# mrShark_11.net
KiCad netlist of a schematic drawn in EAGLE
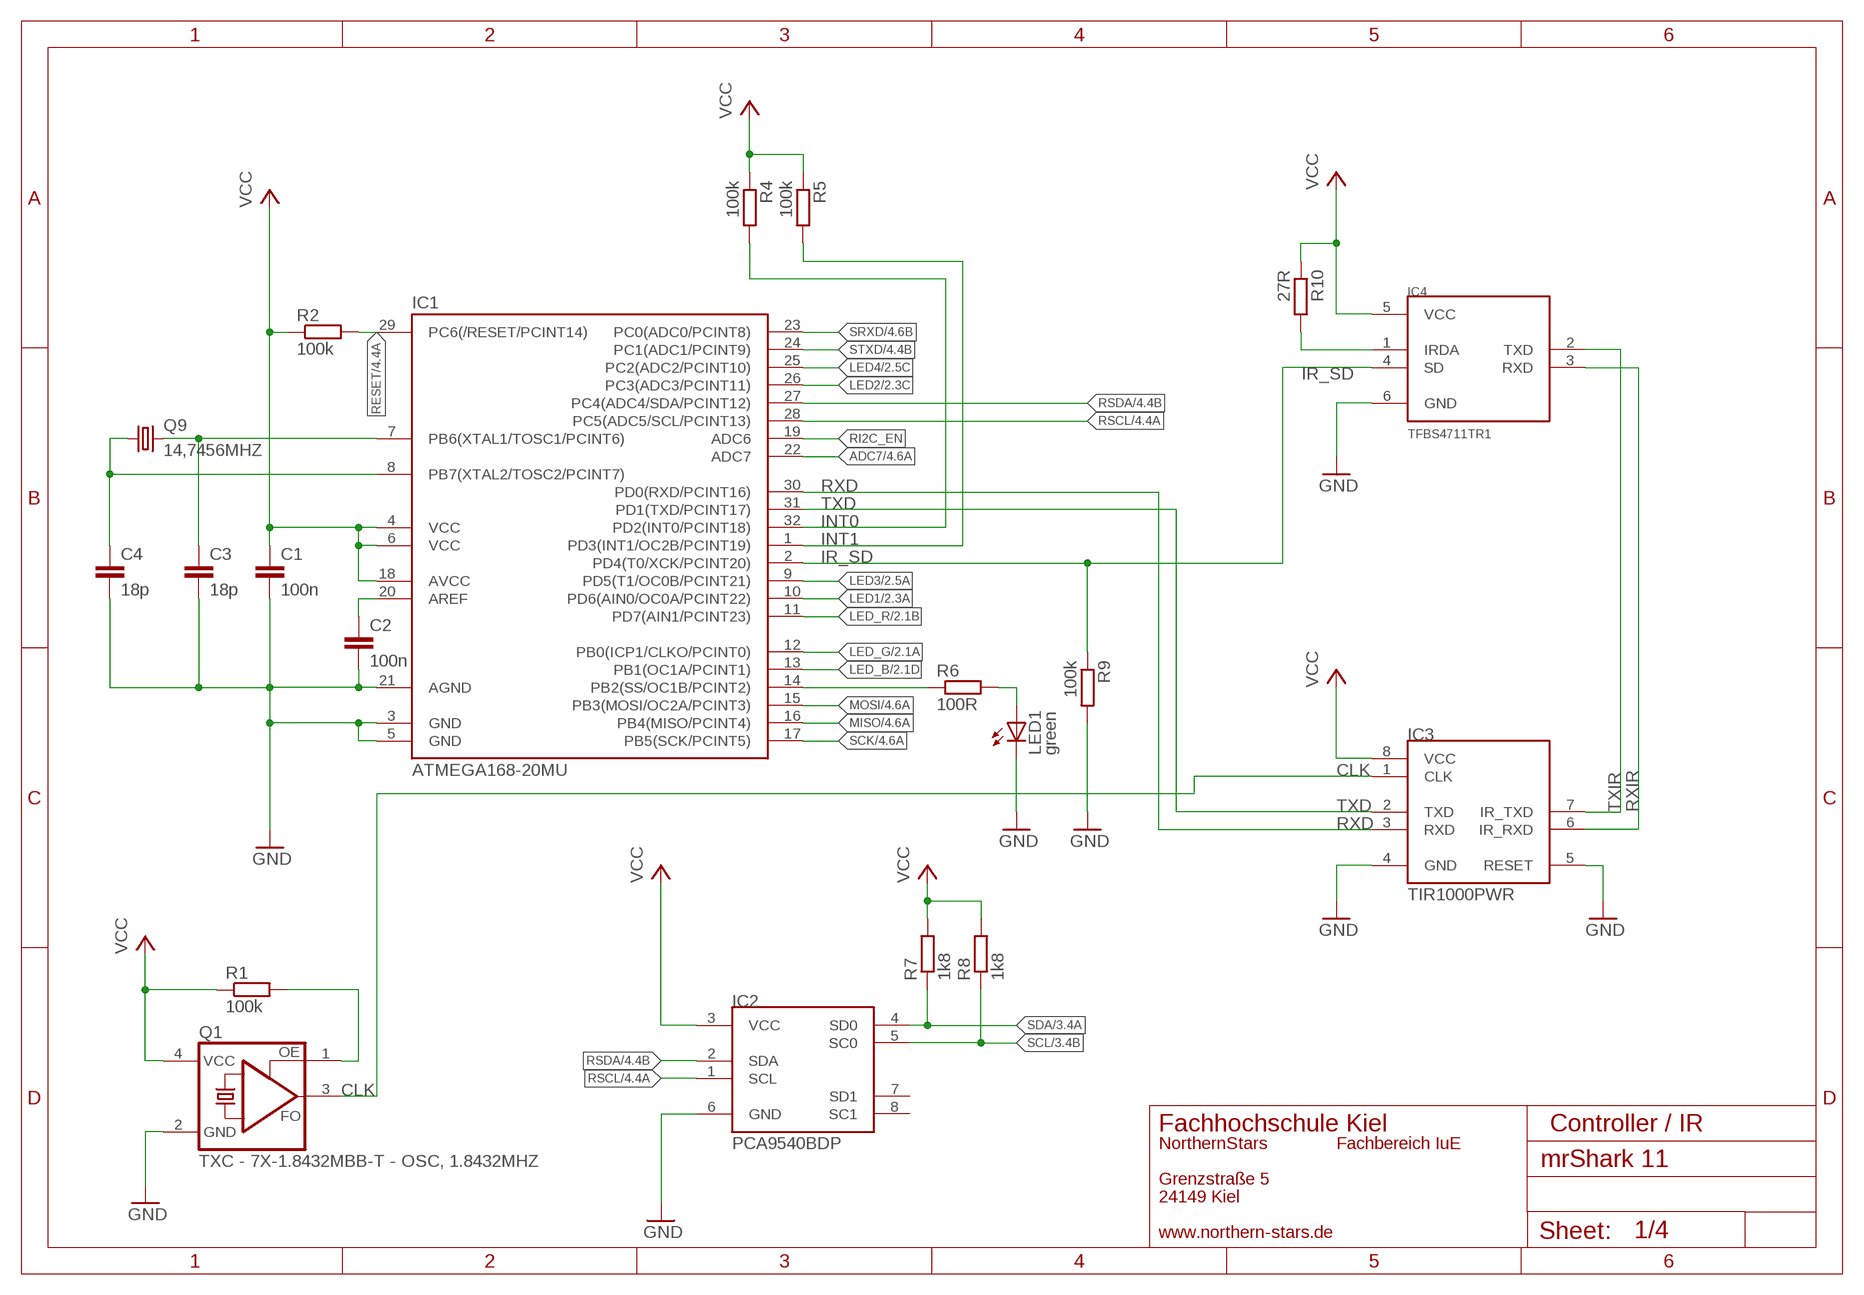
[diagram p0: schematic, sheet 1]
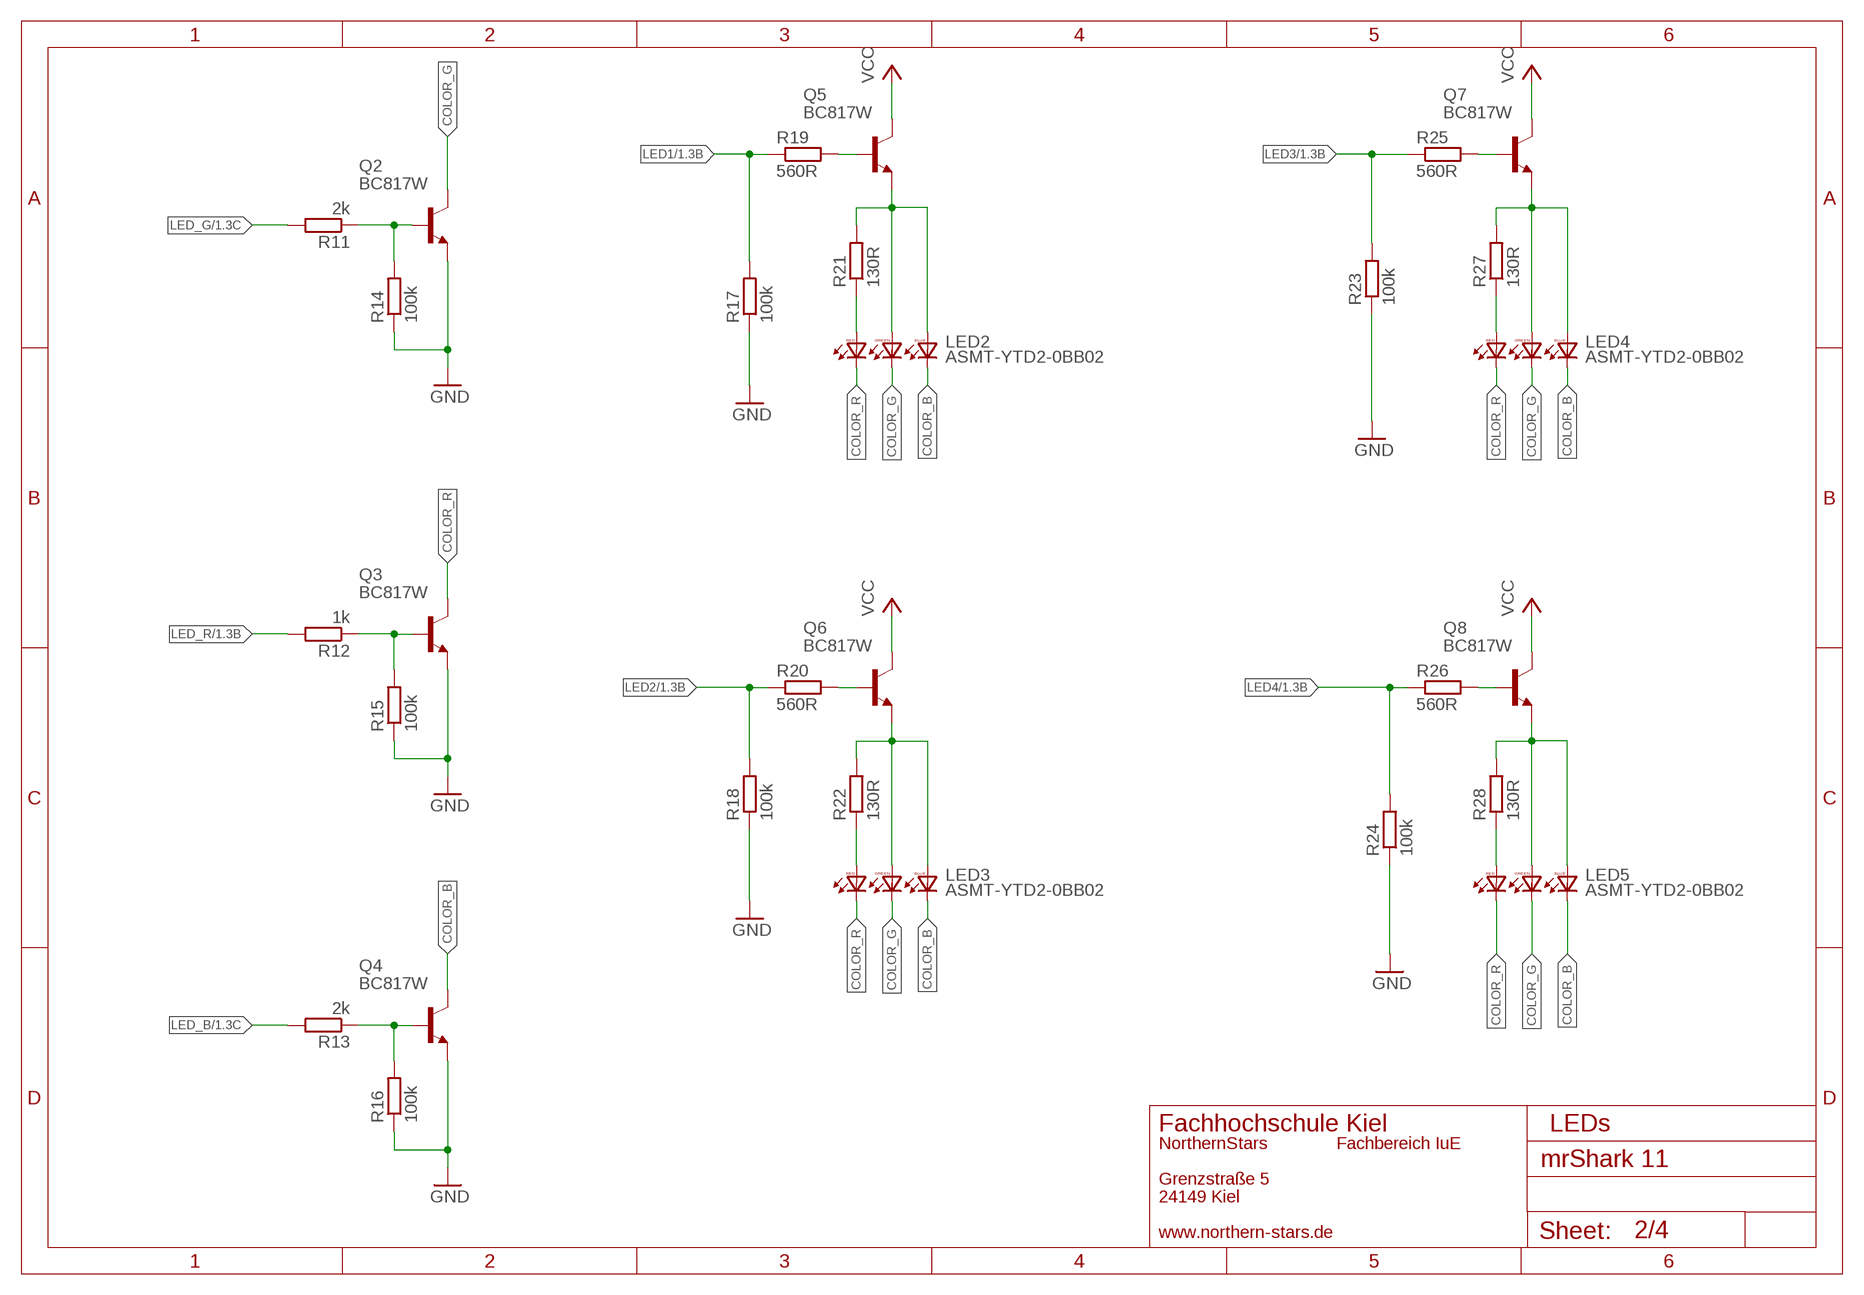
[diagram p1: schematic, sheet 2]
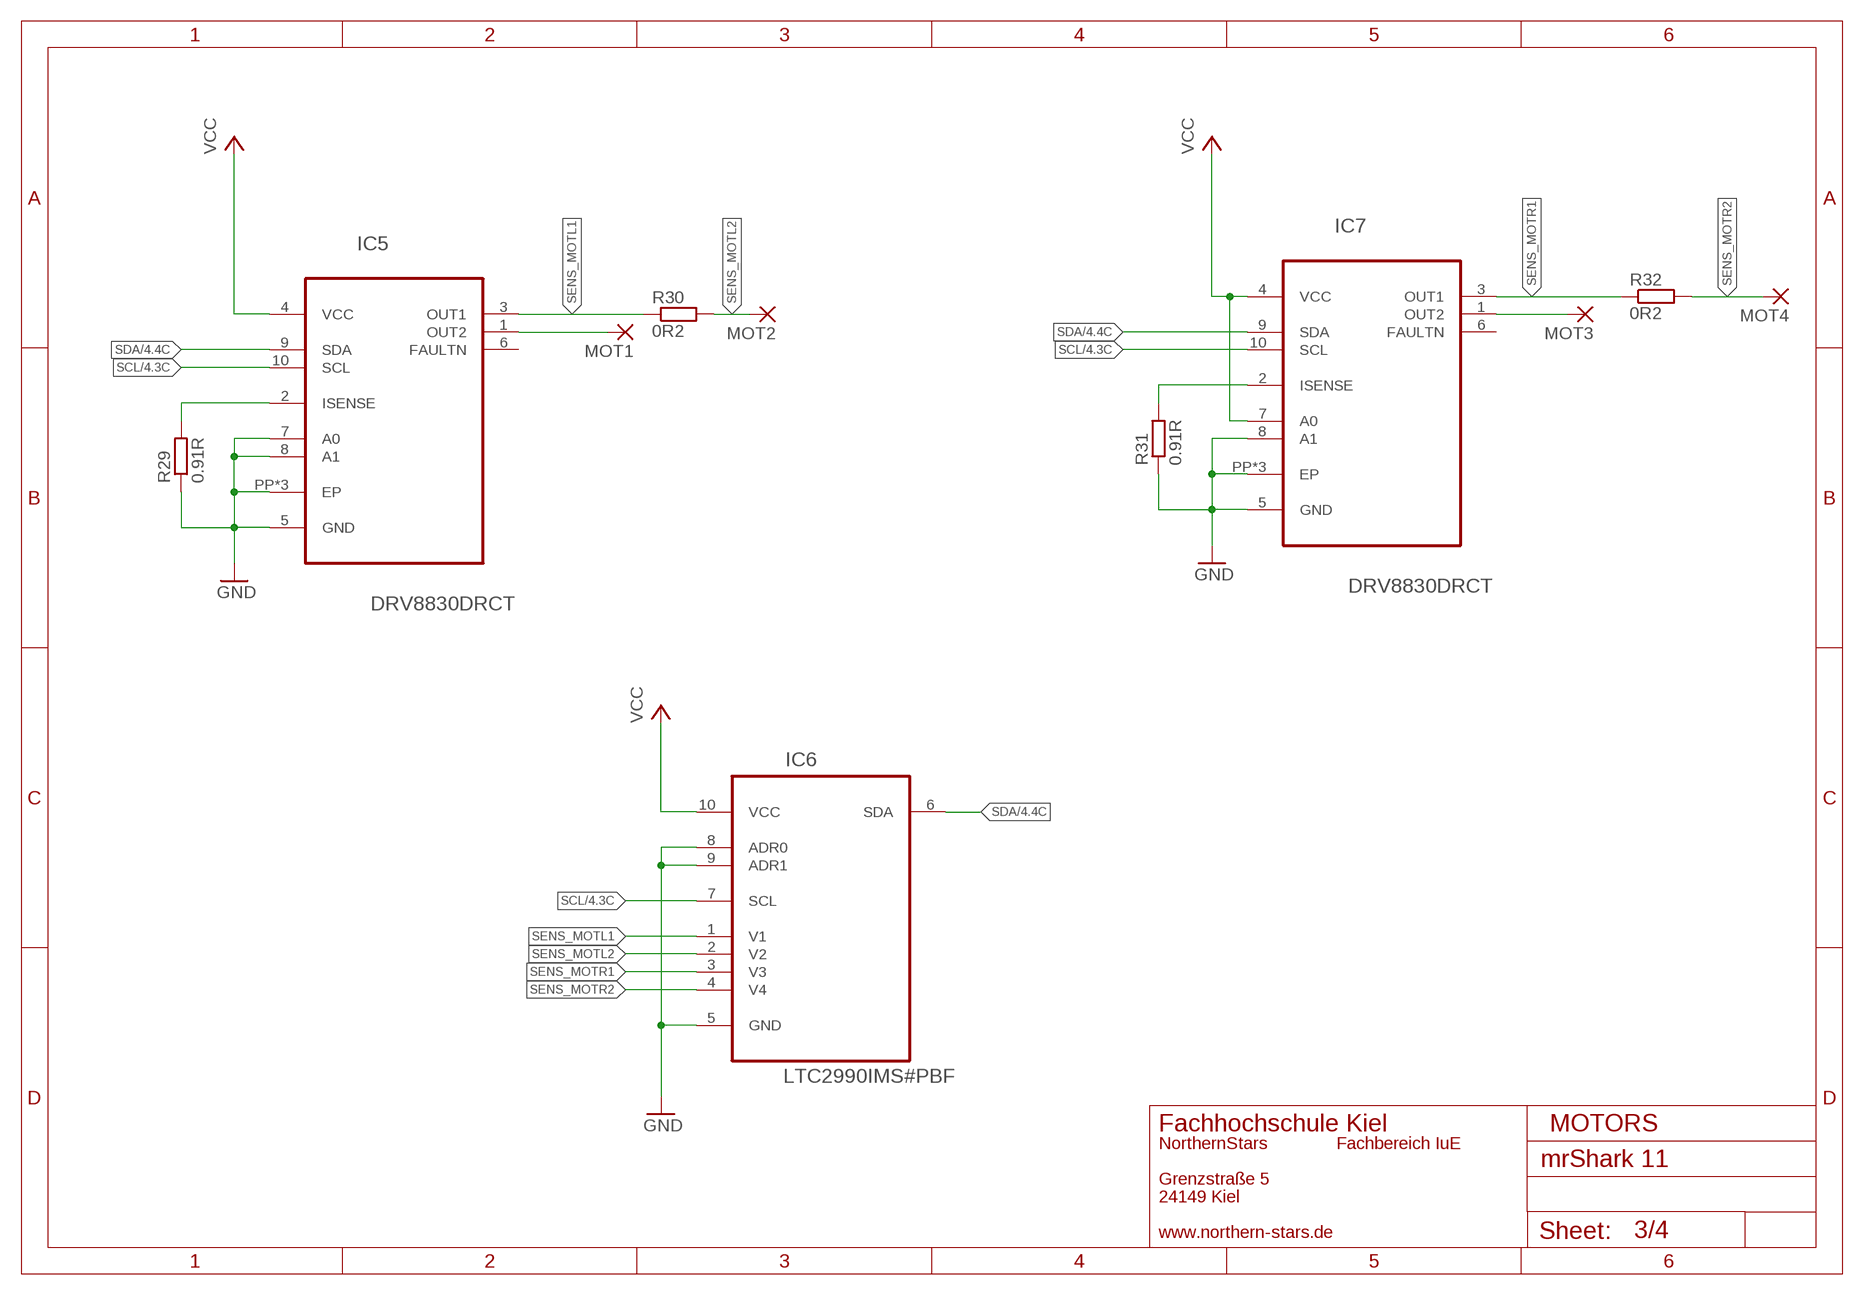
[diagram p2: schematic, sheet 3]
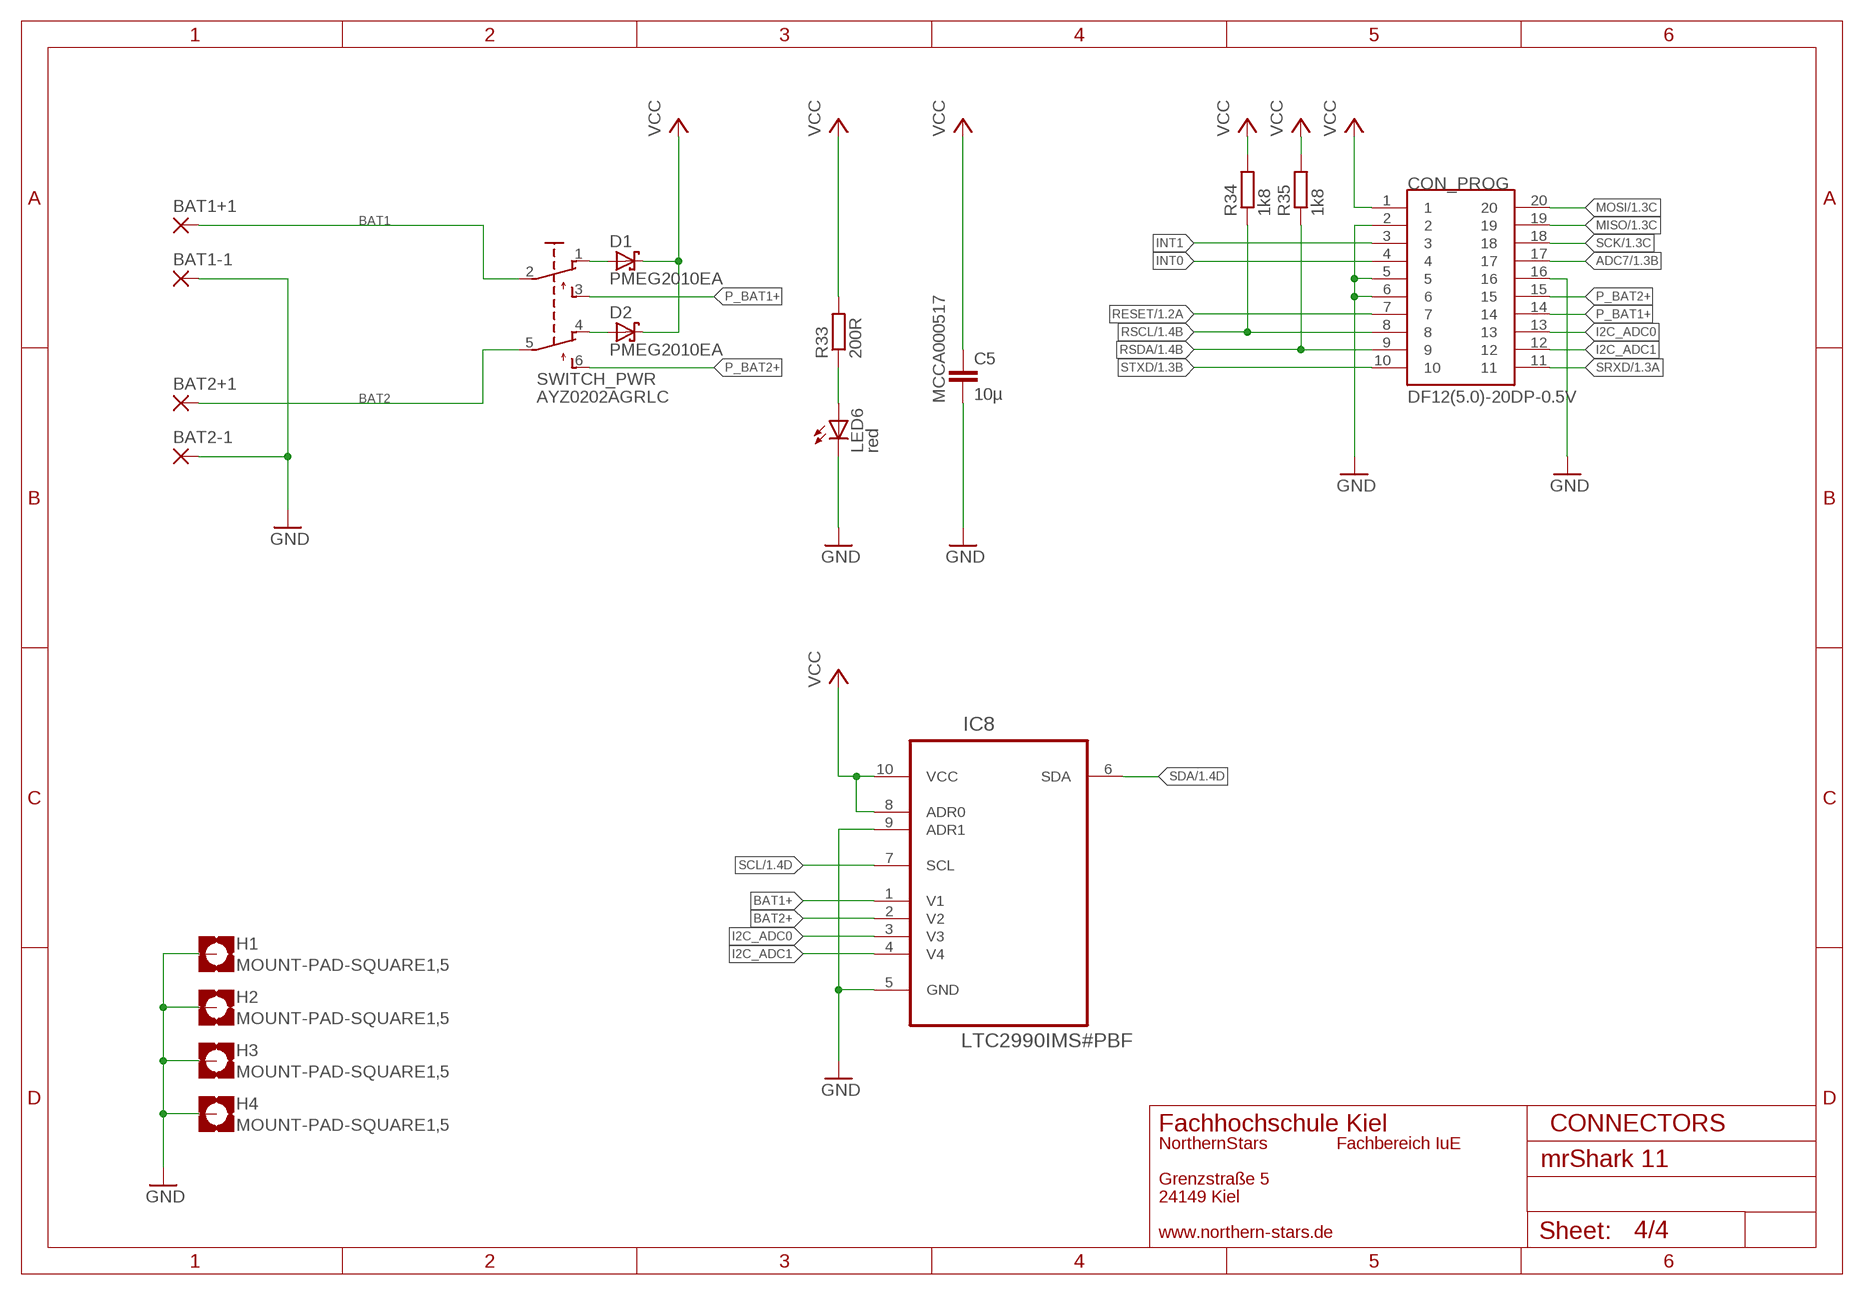
[diagram p3: schematic, sheet 4]

(export (version "E")
  (design (tool "Eeschema 10.0.6"))
  (components
    (comp (ref "IC5")
      (value "DRV8830DRCT")
      (footprint "eagle-import:S-PDSO-N10")
      (libsource (lib "eagle-import") (part "DRV8830DGQRWSON"))
    )
    (comp (ref "IC6")
      (value "LTC2990IMS#PBF")
      (footprint "eagle-import:SOP50P490X110-10N")
      (libsource (lib "eagle-import") (part "LTC2990IMSPBF"))
    )
    (comp (ref "IC7")
      (value "DRV8830DRCT")
      (footprint "eagle-import:S-PDSO-N10")
      (libsource (lib "eagle-import") (part "DRV8830DGQRWSON"))
    )
    (comp (ref "MOT1")
      (value "1,6/0,9")
      (footprint "eagle-import:1,6_0,9")
      (libsource (lib "eagle-import") (part "1,6/0,9"))
    )
    (comp (ref "MOT2")
      (value "1,6/0,9")
      (footprint "eagle-import:1,6_0,9")
      (libsource (lib "eagle-import") (part "1,6/0,9"))
    )
    (comp (ref "MOT3")
      (value "1,6/0,9")
      (footprint "eagle-import:1,6_0,9")
      (libsource (lib "eagle-import") (part "1,6/0,9"))
    )
    (comp (ref "MOT4")
      (value "1,6/0,9")
      (footprint "eagle-import:1,6_0,9")
      (libsource (lib "eagle-import") (part "1,6/0,9"))
    )
    (comp (ref "R29")
      (value "0.91R")
      (footprint "eagle-import:R0603")
      (libsource (lib "eagle-import") (part "R-EU_R0603"))
    )
    (comp (ref "R30")
      (value "0R2")
      (footprint "eagle-import:R0603")
      (libsource (lib "eagle-import") (part "R-EU_R0603"))
    )
    (comp (ref "R31")
      (value "0.91R")
      (footprint "eagle-import:R0603")
      (libsource (lib "eagle-import") (part "R-EU_R0603"))
    )
    (comp (ref "R32")
      (value "0R2")
      (footprint "eagle-import:R0603")
      (libsource (lib "eagle-import") (part "R-EU_R0603"))
    )
    (comp (ref "LED2")
      (value "ASMT-YTD2-0BB02")
      (footprint "eagle-import:PLCC6K")
      (libsource (lib "eagle-import") (part "PLCC6K"))
    )
    (comp (ref "LED3")
      (value "ASMT-YTD2-0BB02")
      (footprint "eagle-import:PLCC6K")
      (libsource (lib "eagle-import") (part "PLCC6K"))
    )
    (comp (ref "LED4")
      (value "ASMT-YTD2-0BB02")
      (footprint "eagle-import:PLCC6K")
      (libsource (lib "eagle-import") (part "PLCC6K"))
    )
    (comp (ref "LED5")
      (value "ASMT-YTD2-0BB02")
      (footprint "eagle-import:PLCC6K")
      (libsource (lib "eagle-import") (part "PLCC6K"))
    )
    (comp (ref "Q2")
      (value "BC817W")
      (footprint "eagle-import:SOT323-BEC")
      (libsource (lib "eagle-import") (part "BC817W"))
    )
    (comp (ref "Q3")
      (value "BC817W")
      (footprint "eagle-import:SOT323-BEC")
      (libsource (lib "eagle-import") (part "BC817W"))
    )
    (comp (ref "Q4")
      (value "BC817W")
      (footprint "eagle-import:SOT323-BEC")
      (libsource (lib "eagle-import") (part "BC817W"))
    )
    (comp (ref "Q5")
      (value "BC817W")
      (footprint "eagle-import:SOT323-BEC")
      (libsource (lib "eagle-import") (part "BC817W"))
    )
    (comp (ref "Q6")
      (value "BC817W")
      (footprint "eagle-import:SOT323-BEC")
      (libsource (lib "eagle-import") (part "BC817W"))
    )
    (comp (ref "Q7")
      (value "BC817W")
      (footprint "eagle-import:SOT323-BEC")
      (libsource (lib "eagle-import") (part "BC817W"))
    )
    (comp (ref "Q8")
      (value "BC817W")
      (footprint "eagle-import:SOT323-BEC")
      (libsource (lib "eagle-import") (part "BC817W"))
    )
    (comp (ref "R11")
      (value "2k")
      (footprint "eagle-import:R0201")
      (libsource (lib "eagle-import") (part "R-EU_R0201"))
    )
    (comp (ref "R12")
      (value "1k")
      (footprint "eagle-import:R0201")
      (libsource (lib "eagle-import") (part "R-EU_R0201"))
    )
    (comp (ref "R13")
      (value "2k")
      (footprint "eagle-import:R0201")
      (libsource (lib "eagle-import") (part "R-EU_R0201"))
    )
    (comp (ref "R14")
      (value "100k")
      (footprint "eagle-import:R0201")
      (libsource (lib "eagle-import") (part "R-EU_R0201"))
    )
    (comp (ref "R15")
      (value "100k")
      (footprint "eagle-import:R0201")
      (libsource (lib "eagle-import") (part "R-EU_R0201"))
    )
    (comp (ref "R16")
      (value "100k")
      (footprint "eagle-import:R0201")
      (libsource (lib "eagle-import") (part "R-EU_R0201"))
    )
    (comp (ref "R17")
      (value "100k")
      (footprint "eagle-import:R0201")
      (libsource (lib "eagle-import") (part "R-EU_R0201"))
    )
    (comp (ref "R18")
      (value "100k")
      (footprint "eagle-import:R0201")
      (libsource (lib "eagle-import") (part "R-EU_R0201"))
    )
    (comp (ref "R19")
      (value "560R")
      (footprint "eagle-import:R0201")
      (libsource (lib "eagle-import") (part "R-EU_R0201"))
    )
    (comp (ref "R20")
      (value "560R")
      (footprint "eagle-import:R0201")
      (libsource (lib "eagle-import") (part "R-EU_R0201"))
    )
    (comp (ref "R21")
      (value "130R")
      (footprint "eagle-import:R0201")
      (libsource (lib "eagle-import") (part "R-EU_R0201"))
    )
    (comp (ref "R22")
      (value "130R")
      (footprint "eagle-import:R0201")
      (libsource (lib "eagle-import") (part "R-EU_R0201"))
    )
    (comp (ref "R23")
      (value "100k")
      (footprint "eagle-import:R0201")
      (libsource (lib "eagle-import") (part "R-EU_R0201"))
    )
    (comp (ref "R24")
      (value "100k")
      (footprint "eagle-import:R0201")
      (libsource (lib "eagle-import") (part "R-EU_R0201"))
    )
    (comp (ref "R25")
      (value "560R")
      (footprint "eagle-import:R0201")
      (libsource (lib "eagle-import") (part "R-EU_R0201"))
    )
    (comp (ref "R26")
      (value "560R")
      (footprint "eagle-import:R0201")
      (libsource (lib "eagle-import") (part "R-EU_R0201"))
    )
    (comp (ref "R27")
      (value "130R")
      (footprint "eagle-import:R0201")
      (libsource (lib "eagle-import") (part "R-EU_R0201"))
    )
    (comp (ref "R28")
      (value "130R")
      (footprint "eagle-import:R0201")
      (libsource (lib "eagle-import") (part "R-EU_R0201"))
    )
    (comp (ref "C1")
      (value "100n")
      (footprint "eagle-import:C0201")
      (libsource (lib "eagle-import") (part "C-EUC0201"))
    )
    (comp (ref "C2")
      (value "100n")
      (footprint "eagle-import:C0201")
      (libsource (lib "eagle-import") (part "C-EUC0201"))
    )
    (comp (ref "C3")
      (value "18p")
      (footprint "eagle-import:C0201")
      (libsource (lib "eagle-import") (part "C-EUC0201"))
    )
    (comp (ref "C4")
      (value "18p")
      (footprint "eagle-import:C0201")
      (libsource (lib "eagle-import") (part "C-EUC0201"))
    )
    (comp (ref "IC1")
      (value "ATMEGA168-20MU")
      (footprint "eagle-import:MLF32")
      (libsource (lib "eagle-import") (part "ATMEGA48/88/168-MU"))
    )
    (comp (ref "IC2")
      (value "PCA9540BDP")
      (footprint "eagle-import:TSSOP8")
      (libsource (lib "eagle-import") (part "PCA9540TSSOP8"))
    )
    (comp (ref "IC3")
      (value "TIR1000PWR")
      (footprint "eagle-import:PW_R-PDSO-G08")
      (libsource (lib "eagle-import") (part "TIR1000PWR"))
    )
    (comp (ref "IC4")
      (value "TFBS4711TR1")
      (footprint "eagle-import:TFBS4711")
      (libsource (lib "eagle-import") (part "TFBS4711TR1"))
    )
    (comp (ref "LED1")
      (value "green")
      (footprint "eagle-import:CHIPLED_0603")
      (libsource (lib "eagle-import") (part "LEDCHIPLED_0603"))
    )
    (comp (ref "Q1")
      (value "TXC - 7X-1.8432MBB-T - OSC, 1.8432MHZ")
      (footprint "eagle-import:3.2X2.5")
      (libsource (lib "eagle-import") (part "7X-SERIES"))
    )
    (comp (ref "Q9")
      (value "14,7456MHZ")
      (footprint "eagle-import:TXC_7B_SERIES")
      (libsource (lib "eagle-import") (part "TXC-7B-SERIESSMD"))
    )
    (comp (ref "R1")
      (value "100k")
      (footprint "eagle-import:R0201")
      (libsource (lib "eagle-import") (part "R-EU_R0201"))
    )
    (comp (ref "R2")
      (value "100k")
      (footprint "eagle-import:R0201")
      (libsource (lib "eagle-import") (part "R-EU_R0201"))
    )
    (comp (ref "R4")
      (value "100k")
      (footprint "eagle-import:R0201")
      (libsource (lib "eagle-import") (part "R-EU_R0201"))
    )
    (comp (ref "R5")
      (value "100k")
      (footprint "eagle-import:R0201")
      (libsource (lib "eagle-import") (part "R-EU_R0201"))
    )
    (comp (ref "R6")
      (value "100R")
      (footprint "eagle-import:R0201")
      (libsource (lib "eagle-import") (part "R-EU_R0201"))
    )
    (comp (ref "R7")
      (value "1k8")
      (footprint "eagle-import:R0201")
      (libsource (lib "eagle-import") (part "R-EU_R0201"))
    )
    (comp (ref "R8")
      (value "1k8")
      (footprint "eagle-import:R0201")
      (libsource (lib "eagle-import") (part "R-EU_R0201"))
    )
    (comp (ref "R9")
      (value "100k")
      (footprint "eagle-import:R0201")
      (libsource (lib "eagle-import") (part "R-EU_R0201"))
    )
    (comp (ref "R10")
      (value "27R")
      (footprint "eagle-import:R0201")
      (libsource (lib "eagle-import") (part "R-EU_R0201"))
    )
    (comp (ref "BAT1+1")
      (value "1,6/0,9")
      (footprint "eagle-import:1,6_0,9")
      (libsource (lib "eagle-import") (part "1,6/0,9"))
    )
    (comp (ref "BAT1-1")
      (value "1,6/0,9")
      (footprint "eagle-import:1,6_0,9")
      (libsource (lib "eagle-import") (part "1,6/0,9"))
    )
    (comp (ref "BAT2+1")
      (value "1,6/0,9")
      (footprint "eagle-import:1,6_0,9")
      (libsource (lib "eagle-import") (part "1,6/0,9"))
    )
    (comp (ref "BAT2-1")
      (value "1,6/0,9")
      (footprint "eagle-import:1,6_0,9")
      (libsource (lib "eagle-import") (part "1,6/0,9"))
    )
    (comp (ref "C5")
      (value "10µ")
      (footprint "eagle-import:C0603K")
      (libsource (lib "eagle-import") (part "C-EUC0603K"))
    )
    (comp (ref "CON_PROG")
      (value "DF12(5.0)-20DP-0.5V")
      (footprint "eagle-import:DF12-20DP")
      (libsource (lib "eagle-import") (part "DF12-20DP"))
    )
    (comp (ref "D1")
      (value "PMEG2010EA")
      (footprint "eagle-import:SOD323-R")
      (libsource (lib "eagle-import") (part "PMEG2010EAR"))
    )
    (comp (ref "D2")
      (value "PMEG2010EA")
      (footprint "eagle-import:SOD323-R")
      (libsource (lib "eagle-import") (part "PMEG2010EAR"))
    )
    (comp (ref "H1")
      (value "MOUNT-PAD-SQUARE1,5")
      (footprint "eagle-import:0,75-PAD-SQUARE")
      (libsource (lib "eagle-import") (part "MOUNT-PAD-SQUARE1,5"))
    )
    (comp (ref "H2")
      (value "MOUNT-PAD-SQUARE1,5")
      (footprint "eagle-import:0,75-PAD-SQUARE")
      (libsource (lib "eagle-import") (part "MOUNT-PAD-SQUARE1,5"))
    )
    (comp (ref "H3")
      (value "MOUNT-PAD-SQUARE1,5")
      (footprint "eagle-import:0,75-PAD-SQUARE")
      (libsource (lib "eagle-import") (part "MOUNT-PAD-SQUARE1,5"))
    )
    (comp (ref "H4")
      (value "MOUNT-PAD-SQUARE1,5")
      (footprint "eagle-import:0,75-PAD-SQUARE")
      (libsource (lib "eagle-import") (part "MOUNT-PAD-SQUARE1,5"))
    )
    (comp (ref "IC8")
      (value "LTC2990IMS#PBF")
      (footprint "eagle-import:SOP50P490X110-10N")
      (libsource (lib "eagle-import") (part "LTC2990IMSPBF"))
    )
    (comp (ref "LED6")
      (value "red")
      (footprint "eagle-import:CHIPLED_0603")
      (libsource (lib "eagle-import") (part "LEDCHIPLED_0603"))
    )
    (comp (ref "R33")
      (value "200R")
      (footprint "eagle-import:R0201")
      (libsource (lib "eagle-import") (part "R-EU_R0201"))
    )
    (comp (ref "R34")
      (value "1k8")
      (footprint "eagle-import:R0201")
      (libsource (lib "eagle-import") (part "R-EU_R0201"))
    )
    (comp (ref "R35")
      (value "1k8")
      (footprint "eagle-import:R0201")
      (libsource (lib "eagle-import") (part "R-EU_R0201"))
    )
    (comp (ref "SWITCH_PWR")
      (value "AYZ0202AGRLC")
      (footprint "eagle-import:AYZ0202AGLRC")
      (libsource (lib "eagle-import") (part "AYZ0202AGRLC"))
    )
  )
  (nets
    (net (code "1") (name "ADC7") (class "Default")
      (node (ref "CON_PROG") (pin "17") (pinfunction "17_17") (pintype "bidirectional"))
      (node (ref "IC1") (pin "22") (pinfunction "ADC7_22") (pintype "passive"))
    )
    (net (code "2") (name "BAT1") (class "Default")
      (node (ref "BAT1+1") (pin "1") (pinfunction "P_1") (pintype "passive"))
      (node (ref "SWITCH_PWR") (pin "2") (pinfunction "P_2") (pintype "passive"))
    )
    (net (code "3") (name "BAT1+") (class "Default")
      (node (ref "D1") (pin "A") (pinfunction "A_A") (pintype "passive"))
      (node (ref "IC8") (pin "1") (pinfunction "V1_1") (pintype "input"))
      (node (ref "SWITCH_PWR") (pin "1") (pinfunction "O_1") (pintype "passive"))
    )
    (net (code "4") (name "BAT2") (class "Default")
      (node (ref "BAT2+1") (pin "1") (pinfunction "P_1") (pintype "passive"))
      (node (ref "SWITCH_PWR") (pin "5") (pinfunction "P1_5") (pintype "passive"))
    )
    (net (code "5") (name "BAT2+") (class "Default")
      (node (ref "D2") (pin "A") (pinfunction "A_A") (pintype "passive"))
      (node (ref "IC8") (pin "2") (pinfunction "V2_2") (pintype "input"))
      (node (ref "SWITCH_PWR") (pin "4") (pinfunction "O1_4") (pintype "passive"))
    )
    (net (code "6") (name "CLK") (class "Default")
      (node (ref "IC3") (pin "1") (pinfunction "CLK_1") (pintype "bidirectional"))
      (node (ref "Q1") (pin "3") (pinfunction "FO_3") (pintype "output"))
    )
    (net (code "7") (name "COLOR_B") (class "Default")
      (node (ref "LED2") (pin "1") (pinfunction "BC_1") (pintype "passive"))
      (node (ref "LED3") (pin "1") (pinfunction "BC_1") (pintype "passive"))
      (node (ref "LED4") (pin "1") (pinfunction "BC_1") (pintype "passive"))
      (node (ref "LED5") (pin "1") (pinfunction "BC_1") (pintype "passive"))
      (node (ref "Q4") (pin "C") (pinfunction "C_C") (pintype "passive"))
    )
    (net (code "8") (name "COLOR_G") (class "Default")
      (node (ref "LED2") (pin "2") (pinfunction "GC_2") (pintype "passive"))
      (node (ref "LED3") (pin "2") (pinfunction "GC_2") (pintype "passive"))
      (node (ref "LED4") (pin "2") (pinfunction "GC_2") (pintype "passive"))
      (node (ref "LED5") (pin "2") (pinfunction "GC_2") (pintype "passive"))
      (node (ref "Q2") (pin "C") (pinfunction "C_C") (pintype "passive"))
    )
    (net (code "9") (name "COLOR_R") (class "Default")
      (node (ref "LED2") (pin "3") (pinfunction "RC_3") (pintype "passive"))
      (node (ref "LED3") (pin "3") (pinfunction "RC_3") (pintype "passive"))
      (node (ref "LED4") (pin "3") (pinfunction "RC_3") (pintype "passive"))
      (node (ref "LED5") (pin "3") (pinfunction "RC_3") (pintype "passive"))
      (node (ref "Q3") (pin "C") (pinfunction "C_C") (pintype "passive"))
    )
    (net (code "10") (name "GND") (class "Default")
      (node (ref "BAT1-1") (pin "1") (pinfunction "P_1") (pintype "passive"))
      (node (ref "BAT2-1") (pin "1") (pinfunction "P_1") (pintype "passive"))
      (node (ref "C1") (pin "2") (pinfunction "2_2") (pintype "passive"))
      (node (ref "C2") (pin "2") (pinfunction "2_2") (pintype "passive"))
      (node (ref "C3") (pin "2") (pinfunction "2_2") (pintype "passive"))
      (node (ref "C4") (pin "2") (pinfunction "2_2") (pintype "passive"))
      (node (ref "C5") (pin "2") (pinfunction "2_2") (pintype "passive"))
      (node (ref "CON_PROG") (pin "16") (pinfunction "16_16") (pintype "bidirectional"))
      (node (ref "CON_PROG") (pin "2") (pinfunction "2_2") (pintype "bidirectional"))
      (node (ref "CON_PROG") (pin "5") (pinfunction "5_5") (pintype "bidirectional"))
      (node (ref "CON_PROG") (pin "6") (pinfunction "6_6") (pintype "bidirectional"))
      (node (ref "H1") (pin "P") (pinfunction "MOUNT_P") (pintype "passive"))
      (node (ref "H2") (pin "P") (pinfunction "MOUNT_P") (pintype "passive"))
      (node (ref "H3") (pin "P") (pinfunction "MOUNT_P") (pintype "passive"))
      (node (ref "H4") (pin "P") (pinfunction "MOUNT_P") (pintype "passive"))
      (node (ref "IC1") (pin "21") (pinfunction "AGND_21") (pintype "power_in"))
      (node (ref "IC1") (pin "3") (pinfunction "GND_3") (pintype "power_in"))
      (node (ref "IC1") (pin "5") (pinfunction "GND_5") (pintype "power_in"))
      (node (ref "IC2") (pin "6") (pinfunction "GND_6") (pintype "bidirectional"))
      (node (ref "IC3") (pin "4") (pinfunction "GND_4") (pintype "bidirectional"))
      (node (ref "IC3") (pin "5") (pinfunction "RESET_5") (pintype "bidirectional"))
      (node (ref "IC4") (pin "6") (pinfunction "GND_6") (pintype "bidirectional"))
      (node (ref "IC5") (pin "5") (pinfunction "GND_5") (pintype "passive"))
      (node (ref "IC5") (pin "7") (pinfunction "A0_7") (pintype "input"))
      (node (ref "IC5") (pin "8") (pinfunction "A1_8") (pintype "input"))
      (node (ref "IC5") (pin "PP") (pinfunction "EP_PP") (pintype "passive"))
      (node (ref "IC5") (pin "PP@1") (pinfunction "EP_PP@1") (pintype "passive"))
      (node (ref "IC5") (pin "PP@2") (pinfunction "EP_PP@2") (pintype "passive"))
      (node (ref "IC6") (pin "5") (pinfunction "GND_5") (pintype "passive"))
      (node (ref "IC6") (pin "8") (pinfunction "ADR0_8") (pintype "input"))
      (node (ref "IC6") (pin "9") (pinfunction "ADR1_9") (pintype "input"))
      (node (ref "IC7") (pin "5") (pinfunction "GND_5") (pintype "passive"))
      (node (ref "IC7") (pin "8") (pinfunction "A1_8") (pintype "input"))
      (node (ref "IC7") (pin "PP") (pinfunction "EP_PP") (pintype "passive"))
      (node (ref "IC7") (pin "PP@1") (pinfunction "EP_PP@1") (pintype "passive"))
      (node (ref "IC7") (pin "PP@2") (pinfunction "EP_PP@2") (pintype "passive"))
      (node (ref "IC8") (pin "5") (pinfunction "GND_5") (pintype "passive"))
      (node (ref "IC8") (pin "9") (pinfunction "ADR1_9") (pintype "input"))
      (node (ref "LED1") (pin "C") (pinfunction "C_C") (pintype "passive"))
      (node (ref "LED6") (pin "C") (pinfunction "C_C") (pintype "passive"))
      (node (ref "Q1") (pin "2") (pinfunction "GND_2") (pintype "power_in"))
      (node (ref "Q2") (pin "E") (pinfunction "E_E") (pintype "passive"))
      (node (ref "Q3") (pin "E") (pinfunction "E_E") (pintype "passive"))
      (node (ref "Q4") (pin "E") (pinfunction "E_E") (pintype "passive"))
      (node (ref "R14") (pin "1") (pinfunction "1_1") (pintype "passive"))
      (node (ref "R15") (pin "1") (pinfunction "1_1") (pintype "passive"))
      (node (ref "R16") (pin "1") (pinfunction "1_1") (pintype "passive"))
      (node (ref "R17") (pin "1") (pinfunction "1_1") (pintype "passive"))
      (node (ref "R18") (pin "1") (pinfunction "1_1") (pintype "passive"))
      (node (ref "R23") (pin "1") (pinfunction "1_1") (pintype "passive"))
      (node (ref "R24") (pin "1") (pinfunction "1_1") (pintype "passive"))
      (node (ref "R29") (pin "1") (pinfunction "1_1") (pintype "passive"))
      (node (ref "R31") (pin "1") (pinfunction "1_1") (pintype "passive"))
      (node (ref "R9") (pin "2") (pinfunction "2_2") (pintype "passive"))
    )
    (net (code "11") (name "I2C_ADC0") (class "Default")
      (node (ref "CON_PROG") (pin "13") (pinfunction "13_13") (pintype "bidirectional"))
      (node (ref "IC8") (pin "3") (pinfunction "V3_3") (pintype "input"))
    )
    (net (code "12") (name "I2C_ADC1") (class "Default")
      (node (ref "CON_PROG") (pin "12") (pinfunction "12_12") (pintype "bidirectional"))
      (node (ref "IC8") (pin "4") (pinfunction "V4_4") (pintype "input"))
    )
    (net (code "13") (name "INT0") (class "Default")
      (node (ref "CON_PROG") (pin "4") (pinfunction "4_4") (pintype "bidirectional"))
      (node (ref "IC1") (pin "32") (pinfunction "PD2(INT0/PCINT18)_32") (pintype "bidirectional"))
      (node (ref "R4") (pin "2") (pinfunction "2_2") (pintype "passive"))
    )
    (net (code "14") (name "INT1") (class "Default")
      (node (ref "CON_PROG") (pin "3") (pinfunction "3_3") (pintype "bidirectional"))
      (node (ref "IC1") (pin "1") (pinfunction "PD3(INT1/OC2B/PCINT19)_1") (pintype "bidirectional"))
      (node (ref "R5") (pin "2") (pinfunction "2_2") (pintype "passive"))
    )
    (net (code "15") (name "IR_SD") (class "Default")
      (node (ref "IC1") (pin "2") (pinfunction "PD4(T0/XCK/PCINT20)_2") (pintype "bidirectional"))
      (node (ref "IC4") (pin "4") (pinfunction "SD_4") (pintype "bidirectional"))
      (node (ref "R9") (pin "1") (pinfunction "1_1") (pintype "passive"))
    )
    (net (code "16") (name "LED1") (class "Default")
      (node (ref "IC1") (pin "10") (pinfunction "PD6(AIN0/OC0A/PCINT22)_10") (pintype "bidirectional"))
      (node (ref "R17") (pin "2") (pinfunction "2_2") (pintype "passive"))
      (node (ref "R19") (pin "1") (pinfunction "1_1") (pintype "passive"))
    )
    (net (code "17") (name "LED2") (class "Default")
      (node (ref "IC1") (pin "26") (pinfunction "PC3(ADC3/PCINT11)_26") (pintype "bidirectional"))
      (node (ref "R18") (pin "2") (pinfunction "2_2") (pintype "passive"))
      (node (ref "R20") (pin "1") (pinfunction "1_1") (pintype "passive"))
    )
    (net (code "18") (name "LED3") (class "Default")
      (node (ref "IC1") (pin "9") (pinfunction "PD5(T1/OC0B/PCINT21)_9") (pintype "bidirectional"))
      (node (ref "R23") (pin "2") (pinfunction "2_2") (pintype "passive"))
      (node (ref "R25") (pin "1") (pinfunction "1_1") (pintype "passive"))
    )
    (net (code "19") (name "LED4") (class "Default")
      (node (ref "IC1") (pin "25") (pinfunction "PC2(ADC2/PCINT10)_25") (pintype "bidirectional"))
      (node (ref "R24") (pin "2") (pinfunction "2_2") (pintype "passive"))
      (node (ref "R26") (pin "1") (pinfunction "1_1") (pintype "passive"))
    )
    (net (code "20") (name "LED_B") (class "Default")
      (node (ref "IC1") (pin "13") (pinfunction "PB1(OC1A/PCINT1)_13") (pintype "bidirectional"))
      (node (ref "R13") (pin "2") (pinfunction "2_2") (pintype "passive"))
    )
    (net (code "21") (name "LED_G") (class "Default")
      (node (ref "IC1") (pin "12") (pinfunction "PB0(ICP1/CLKO/PCINT0)_12") (pintype "bidirectional"))
      (node (ref "R11") (pin "2") (pinfunction "2_2") (pintype "passive"))
    )
    (net (code "22") (name "LED_R") (class "Default")
      (node (ref "IC1") (pin "11") (pinfunction "PD7(AIN1/PCINT23)_11") (pintype "bidirectional"))
      (node (ref "R12") (pin "2") (pinfunction "2_2") (pintype "passive"))
    )
    (net (code "23") (name "MISO") (class "Default")
      (node (ref "CON_PROG") (pin "19") (pinfunction "19_19") (pintype "bidirectional"))
      (node (ref "IC1") (pin "16") (pinfunction "PB4(MISO/PCINT4)_16") (pintype "bidirectional"))
    )
    (net (code "24") (name "MOSI") (class "Default")
      (node (ref "CON_PROG") (pin "20") (pinfunction "20_20") (pintype "bidirectional"))
      (node (ref "IC1") (pin "15") (pinfunction "PB3(MOSI/OC2A/PCINT3)_15") (pintype "bidirectional"))
    )
    (net (code "25") (name "Net-(IC1-AREF)") (class "Default")
      (node (ref "C2") (pin "1") (pinfunction "1_1") (pintype "passive"))
      (node (ref "IC1") (pin "20") (pinfunction "AREF_20") (pintype "passive"))
    )
    (net (code "26") (name "Net-(IC1-PB2(SS{slash}OC1B{slash}PCINT2))") (class "Default")
      (node (ref "IC1") (pin "14") (pinfunction "PB2(SS/OC1B/PCINT2)_14") (pintype "bidirectional"))
      (node (ref "R6") (pin "1") (pinfunction "1_1") (pintype "passive"))
    )
    (net (code "27") (name "Net-(IC1-PB6(XTAL1{slash}TOSC1{slash}PCINT6))") (class "Default")
      (node (ref "C3") (pin "1") (pinfunction "1_1") (pintype "passive"))
      (node (ref "IC1") (pin "7") (pinfunction "PB6(XTAL1/TOSC1/PCINT6)_7") (pintype "bidirectional"))
      (node (ref "Q9") (pin "3") (pinfunction "2_3") (pintype "passive"))
    )
    (net (code "28") (name "Net-(IC1-PB7(XTAL2{slash}TOSC2{slash}PCINT7))") (class "Default")
      (node (ref "C4") (pin "1") (pinfunction "1_1") (pintype "passive"))
      (node (ref "IC1") (pin "8") (pinfunction "PB7(XTAL2/TOSC2/PCINT7)_8") (pintype "bidirectional"))
      (node (ref "Q9") (pin "1") (pinfunction "1_1") (pintype "passive"))
    )
    (net (code "29") (name "Net-(IC4-IRDA)") (class "Default")
      (node (ref "IC4") (pin "1") (pinfunction "IRDA_1") (pintype "bidirectional"))
      (node (ref "R10") (pin "2") (pinfunction "2_2") (pintype "passive"))
    )
    (net (code "30") (name "Net-(IC5-ISENSE)") (class "Default")
      (node (ref "IC5") (pin "2") (pinfunction "ISENSE_2") (pintype "input"))
      (node (ref "R29") (pin "2") (pinfunction "2_2") (pintype "passive"))
    )
    (net (code "31") (name "Net-(IC5-OUT2)") (class "Default")
      (node (ref "IC5") (pin "1") (pinfunction "OUT2_1") (pintype "output"))
      (node (ref "MOT1") (pin "1") (pinfunction "P_1") (pintype "passive"))
    )
    (net (code "32") (name "Net-(IC7-ISENSE)") (class "Default")
      (node (ref "IC7") (pin "2") (pinfunction "ISENSE_2") (pintype "input"))
      (node (ref "R31") (pin "2") (pinfunction "2_2") (pintype "passive"))
    )
    (net (code "33") (name "Net-(IC7-OUT2)") (class "Default")
      (node (ref "IC7") (pin "1") (pinfunction "OUT2_1") (pintype "output"))
      (node (ref "MOT3") (pin "1") (pinfunction "P_1") (pintype "passive"))
    )
    (net (code "34") (name "Net-(LED1-PadA)") (class "Default")
      (node (ref "LED1") (pin "A") (pinfunction "A_A") (pintype "passive"))
      (node (ref "R6") (pin "2") (pinfunction "2_2") (pintype "passive"))
    )
    (net (code "35") (name "Net-(LED2-BA)") (class "Default")
      (node (ref "LED2") (pin "5") (pinfunction "GA_5") (pintype "passive"))
      (node (ref "LED2") (pin "6") (pinfunction "BA_6") (pintype "passive"))
      (node (ref "Q5") (pin "E") (pinfunction "E_E") (pintype "passive"))
      (node (ref "R21") (pin "2") (pinfunction "2_2") (pintype "passive"))
    )
    (net (code "36") (name "Net-(LED2-RA)") (class "Default")
      (node (ref "LED2") (pin "4") (pinfunction "RA_4") (pintype "passive"))
      (node (ref "R21") (pin "1") (pinfunction "1_1") (pintype "passive"))
    )
    (net (code "37") (name "Net-(LED3-BA)") (class "Default")
      (node (ref "LED3") (pin "5") (pinfunction "GA_5") (pintype "passive"))
      (node (ref "LED3") (pin "6") (pinfunction "BA_6") (pintype "passive"))
      (node (ref "Q6") (pin "E") (pinfunction "E_E") (pintype "passive"))
      (node (ref "R22") (pin "2") (pinfunction "2_2") (pintype "passive"))
    )
    (net (code "38") (name "Net-(LED3-RA)") (class "Default")
      (node (ref "LED3") (pin "4") (pinfunction "RA_4") (pintype "passive"))
      (node (ref "R22") (pin "1") (pinfunction "1_1") (pintype "passive"))
    )
    (net (code "39") (name "Net-(LED4-BA)") (class "Default")
      (node (ref "LED4") (pin "5") (pinfunction "GA_5") (pintype "passive"))
      (node (ref "LED4") (pin "6") (pinfunction "BA_6") (pintype "passive"))
      (node (ref "Q7") (pin "E") (pinfunction "E_E") (pintype "passive"))
      (node (ref "R27") (pin "2") (pinfunction "2_2") (pintype "passive"))
    )
    (net (code "40") (name "Net-(LED4-RA)") (class "Default")
      (node (ref "LED4") (pin "4") (pinfunction "RA_4") (pintype "passive"))
      (node (ref "R27") (pin "1") (pinfunction "1_1") (pintype "passive"))
    )
    (net (code "41") (name "Net-(LED5-BA)") (class "Default")
      (node (ref "LED5") (pin "5") (pinfunction "GA_5") (pintype "passive"))
      (node (ref "LED5") (pin "6") (pinfunction "BA_6") (pintype "passive"))
      (node (ref "Q8") (pin "E") (pinfunction "E_E") (pintype "passive"))
      (node (ref "R28") (pin "2") (pinfunction "2_2") (pintype "passive"))
    )
    (net (code "42") (name "Net-(LED5-RA)") (class "Default")
      (node (ref "LED5") (pin "4") (pinfunction "RA_4") (pintype "passive"))
      (node (ref "R28") (pin "1") (pinfunction "1_1") (pintype "passive"))
    )
    (net (code "43") (name "Net-(LED6-PadA)") (class "Default")
      (node (ref "LED6") (pin "A") (pinfunction "A_A") (pintype "passive"))
      (node (ref "R33") (pin "1") (pinfunction "1_1") (pintype "passive"))
    )
    (net (code "44") (name "Net-(Q1-OE)") (class "Default")
      (node (ref "Q1") (pin "1") (pinfunction "OE_1") (pintype "input"))
      (node (ref "R1") (pin "2") (pinfunction "2_2") (pintype "passive"))
    )
    (net (code "45") (name "Net-(Q2-PadB)") (class "Default")
      (node (ref "Q2") (pin "B") (pinfunction "B_B") (pintype "passive"))
      (node (ref "R11") (pin "1") (pinfunction "1_1") (pintype "passive"))
      (node (ref "R14") (pin "2") (pinfunction "2_2") (pintype "passive"))
    )
    (net (code "46") (name "Net-(Q3-PadB)") (class "Default")
      (node (ref "Q3") (pin "B") (pinfunction "B_B") (pintype "passive"))
      (node (ref "R12") (pin "1") (pinfunction "1_1") (pintype "passive"))
      (node (ref "R15") (pin "2") (pinfunction "2_2") (pintype "passive"))
    )
    (net (code "47") (name "Net-(Q4-PadB)") (class "Default")
      (node (ref "Q4") (pin "B") (pinfunction "B_B") (pintype "passive"))
      (node (ref "R13") (pin "1") (pinfunction "1_1") (pintype "passive"))
      (node (ref "R16") (pin "2") (pinfunction "2_2") (pintype "passive"))
    )
    (net (code "48") (name "Net-(Q5-PadB)") (class "Default")
      (node (ref "Q5") (pin "B") (pinfunction "B_B") (pintype "passive"))
      (node (ref "R19") (pin "2") (pinfunction "2_2") (pintype "passive"))
    )
    (net (code "49") (name "Net-(Q6-PadB)") (class "Default")
      (node (ref "Q6") (pin "B") (pinfunction "B_B") (pintype "passive"))
      (node (ref "R20") (pin "2") (pinfunction "2_2") (pintype "passive"))
    )
    (net (code "50") (name "Net-(Q7-PadB)") (class "Default")
      (node (ref "Q7") (pin "B") (pinfunction "B_B") (pintype "passive"))
      (node (ref "R25") (pin "2") (pinfunction "2_2") (pintype "passive"))
    )
    (net (code "51") (name "Net-(Q8-PadB)") (class "Default")
      (node (ref "Q8") (pin "B") (pinfunction "B_B") (pintype "passive"))
      (node (ref "R26") (pin "2") (pinfunction "2_2") (pintype "passive"))
    )
    (net (code "52") (name "P_BAT1+") (class "Default")
      (node (ref "CON_PROG") (pin "14") (pinfunction "14_14") (pintype "bidirectional"))
      (node (ref "SWITCH_PWR") (pin "3") (pinfunction "S_3") (pintype "passive"))
    )
    (net (code "53") (name "P_BAT2+") (class "Default")
      (node (ref "CON_PROG") (pin "15") (pinfunction "15_15") (pintype "bidirectional"))
      (node (ref "SWITCH_PWR") (pin "6") (pinfunction "S1_6") (pintype "passive"))
    )
    (net (code "54") (name "RESET") (class "Default")
      (node (ref "CON_PROG") (pin "7") (pinfunction "7_7") (pintype "bidirectional"))
      (node (ref "IC1") (pin "29") (pinfunction "PC6(/RESET/PCINT14)_29") (pintype "bidirectional"))
      (node (ref "R2") (pin "2") (pinfunction "2_2") (pintype "passive"))
    )
    (net (code "55") (name "RI2C_EN") (class "Default")
      (node (ref "IC1") (pin "19") (pinfunction "ADC6_19") (pintype "passive"))
    )
    (net (code "56") (name "RSCL") (class "Default")
      (node (ref "CON_PROG") (pin "8") (pinfunction "8_8") (pintype "bidirectional"))
      (node (ref "IC1") (pin "28") (pinfunction "PC5(ADC5/SCL/PCINT13)_28") (pintype "bidirectional"))
      (node (ref "IC2") (pin "1") (pinfunction "SCL_1") (pintype "bidirectional"))
      (node (ref "R34") (pin "1") (pinfunction "1_1") (pintype "passive"))
    )
    (net (code "57") (name "RSDA") (class "Default")
      (node (ref "CON_PROG") (pin "9") (pinfunction "9_9") (pintype "bidirectional"))
      (node (ref "IC1") (pin "27") (pinfunction "PC4(ADC4/SDA/PCINT12)_27") (pintype "bidirectional"))
      (node (ref "IC2") (pin "2") (pinfunction "SDA_2") (pintype "bidirectional"))
      (node (ref "R35") (pin "1") (pinfunction "1_1") (pintype "passive"))
    )
    (net (code "58") (name "RXD") (class "Default")
      (node (ref "IC1") (pin "30") (pinfunction "PD0(RXD/PCINT16)_30") (pintype "bidirectional"))
      (node (ref "IC3") (pin "3") (pinfunction "RXD_3") (pintype "bidirectional"))
    )
    (net (code "59") (name "RXIR") (class "Default")
      (node (ref "IC3") (pin "6") (pinfunction "IR_RXD_6") (pintype "bidirectional"))
      (node (ref "IC4") (pin "3") (pinfunction "RXD_3") (pintype "output"))
    )
    (net (code "60") (name "SCK") (class "Default")
      (node (ref "CON_PROG") (pin "18") (pinfunction "18_18") (pintype "bidirectional"))
      (node (ref "IC1") (pin "17") (pinfunction "PB5(SCK/PCINT5)_17") (pintype "bidirectional"))
    )
    (net (code "61") (name "SCL") (class "Default")
      (node (ref "IC2") (pin "5") (pinfunction "SC0_5") (pintype "bidirectional"))
      (node (ref "IC5") (pin "10") (pinfunction "SCL_10") (pintype "input"))
      (node (ref "IC6") (pin "7") (pinfunction "SCL_7") (pintype "input"))
      (node (ref "IC7") (pin "10") (pinfunction "SCL_10") (pintype "input"))
      (node (ref "IC8") (pin "7") (pinfunction "SCL_7") (pintype "input"))
      (node (ref "R8") (pin "1") (pinfunction "1_1") (pintype "passive"))
    )
    (net (code "62") (name "SDA") (class "Default")
      (node (ref "IC2") (pin "4") (pinfunction "SD0_4") (pintype "bidirectional"))
      (node (ref "IC5") (pin "9") (pinfunction "SDA_9") (pintype "bidirectional"))
      (node (ref "IC6") (pin "6") (pinfunction "SDA_6") (pintype "bidirectional"))
      (node (ref "IC7") (pin "9") (pinfunction "SDA_9") (pintype "bidirectional"))
      (node (ref "IC8") (pin "6") (pinfunction "SDA_6") (pintype "bidirectional"))
      (node (ref "R7") (pin "1") (pinfunction "1_1") (pintype "passive"))
    )
    (net (code "63") (name "SENS_MOTL1") (class "Default")
      (node (ref "IC5") (pin "3") (pinfunction "OUT1_3") (pintype "output"))
      (node (ref "IC6") (pin "1") (pinfunction "V1_1") (pintype "input"))
      (node (ref "R30") (pin "1") (pinfunction "1_1") (pintype "passive"))
    )
    (net (code "64") (name "SENS_MOTL2") (class "Default")
      (node (ref "IC6") (pin "2") (pinfunction "V2_2") (pintype "input"))
      (node (ref "MOT2") (pin "1") (pinfunction "P_1") (pintype "passive"))
      (node (ref "R30") (pin "2") (pinfunction "2_2") (pintype "passive"))
    )
    (net (code "65") (name "SENS_MOTR1") (class "Default")
      (node (ref "IC6") (pin "3") (pinfunction "V3_3") (pintype "input"))
      (node (ref "IC7") (pin "3") (pinfunction "OUT1_3") (pintype "output"))
      (node (ref "R32") (pin "1") (pinfunction "1_1") (pintype "passive"))
    )
    (net (code "66") (name "SENS_MOTR2") (class "Default")
      (node (ref "IC6") (pin "4") (pinfunction "V4_4") (pintype "input"))
      (node (ref "MOT4") (pin "1") (pinfunction "P_1") (pintype "passive"))
      (node (ref "R32") (pin "2") (pinfunction "2_2") (pintype "passive"))
    )
    (net (code "67") (name "SRXD") (class "Default")
      (node (ref "CON_PROG") (pin "11") (pinfunction "11_11") (pintype "bidirectional"))
      (node (ref "IC1") (pin "23") (pinfunction "PC0(ADC0/PCINT8)_23") (pintype "bidirectional"))
    )
    (net (code "68") (name "STXD") (class "Default")
      (node (ref "CON_PROG") (pin "10") (pinfunction "10_10") (pintype "bidirectional"))
      (node (ref "IC1") (pin "24") (pinfunction "PC1(ADC1/PCINT9)_24") (pintype "bidirectional"))
    )
    (net (code "69") (name "TXD") (class "Default")
      (node (ref "IC1") (pin "31") (pinfunction "PD1(TXD/PCINT17)_31") (pintype "bidirectional"))
      (node (ref "IC3") (pin "2") (pinfunction "TXD_2") (pintype "bidirectional"))
    )
    (net (code "70") (name "TXIR") (class "Default")
      (node (ref "IC3") (pin "7") (pinfunction "IR_TXD_7") (pintype "bidirectional"))
      (node (ref "IC4") (pin "2") (pinfunction "TXD_2") (pintype "input"))
    )
    (net (code "71") (name "VCC") (class "Default")
      (node (ref "C1") (pin "1") (pinfunction "1_1") (pintype "passive"))
      (node (ref "C5") (pin "1") (pinfunction "1_1") (pintype "passive"))
      (node (ref "CON_PROG") (pin "1") (pinfunction "1_1") (pintype "bidirectional"))
      (node (ref "D1") (pin "C") (pinfunction "C_C") (pintype "passive"))
      (node (ref "D2") (pin "C") (pinfunction "C_C") (pintype "passive"))
      (node (ref "IC1") (pin "18") (pinfunction "AVCC_18") (pintype "passive"))
      (node (ref "IC1") (pin "4") (pinfunction "VCC_4") (pintype "power_in"))
      (node (ref "IC1") (pin "6") (pinfunction "VCC_6") (pintype "power_in"))
      (node (ref "IC2") (pin "3") (pinfunction "VCC_3") (pintype "bidirectional"))
      (node (ref "IC3") (pin "8") (pinfunction "VCC_8") (pintype "bidirectional"))
      (node (ref "IC4") (pin "5") (pinfunction "VCC_5") (pintype "power_in"))
      (node (ref "IC5") (pin "4") (pinfunction "VCC_4") (pintype "power_in"))
      (node (ref "IC6") (pin "10") (pinfunction "VCC_10") (pintype "power_in"))
      (node (ref "IC7") (pin "4") (pinfunction "VCC_4") (pintype "power_in"))
      (node (ref "IC7") (pin "7") (pinfunction "A0_7") (pintype "input"))
      (node (ref "IC8") (pin "10") (pinfunction "VCC_10") (pintype "power_in"))
      (node (ref "IC8") (pin "8") (pinfunction "ADR0_8") (pintype "input"))
      (node (ref "Q1") (pin "4") (pinfunction "VCC_4") (pintype "power_in"))
      (node (ref "Q5") (pin "C") (pinfunction "C_C") (pintype "passive"))
      (node (ref "Q6") (pin "C") (pinfunction "C_C") (pintype "passive"))
      (node (ref "Q7") (pin "C") (pinfunction "C_C") (pintype "passive"))
      (node (ref "Q8") (pin "C") (pinfunction "C_C") (pintype "passive"))
      (node (ref "R1") (pin "1") (pinfunction "1_1") (pintype "passive"))
      (node (ref "R10") (pin "1") (pinfunction "1_1") (pintype "passive"))
      (node (ref "R2") (pin "1") (pinfunction "1_1") (pintype "passive"))
      (node (ref "R33") (pin "2") (pinfunction "2_2") (pintype "passive"))
      (node (ref "R34") (pin "2") (pinfunction "2_2") (pintype "passive"))
      (node (ref "R35") (pin "2") (pinfunction "2_2") (pintype "passive"))
      (node (ref "R4") (pin "1") (pinfunction "1_1") (pintype "passive"))
      (node (ref "R5") (pin "1") (pinfunction "1_1") (pintype "passive"))
      (node (ref "R7") (pin "2") (pinfunction "2_2") (pintype "passive"))
      (node (ref "R8") (pin "2") (pinfunction "2_2") (pintype "passive"))
    )
    (net (code "72") (name "unconnected-(IC2-SC1-Pad8)") (class "Default")
      (node (ref "IC2") (pin "8") (pinfunction "SC1_8") (pintype "bidirectional"))
    )
    (net (code "73") (name "unconnected-(IC2-SD1-Pad7)") (class "Default")
      (node (ref "IC2") (pin "7") (pinfunction "SD1_7") (pintype "bidirectional"))
    )
    (net (code "74") (name "unconnected-(IC5-FAULTN-Pad6)") (class "Default")
      (node (ref "IC5") (pin "6") (pinfunction "FAULTN_6") (pintype "output"))
    )
    (net (code "75") (name "unconnected-(IC7-FAULTN-Pad6)") (class "Default")
      (node (ref "IC7") (pin "6") (pinfunction "FAULTN_6") (pintype "output"))
    )
  )
)
